# DCSource4V3.net
KiCad netlist of a schematic drawn in Altium Designer
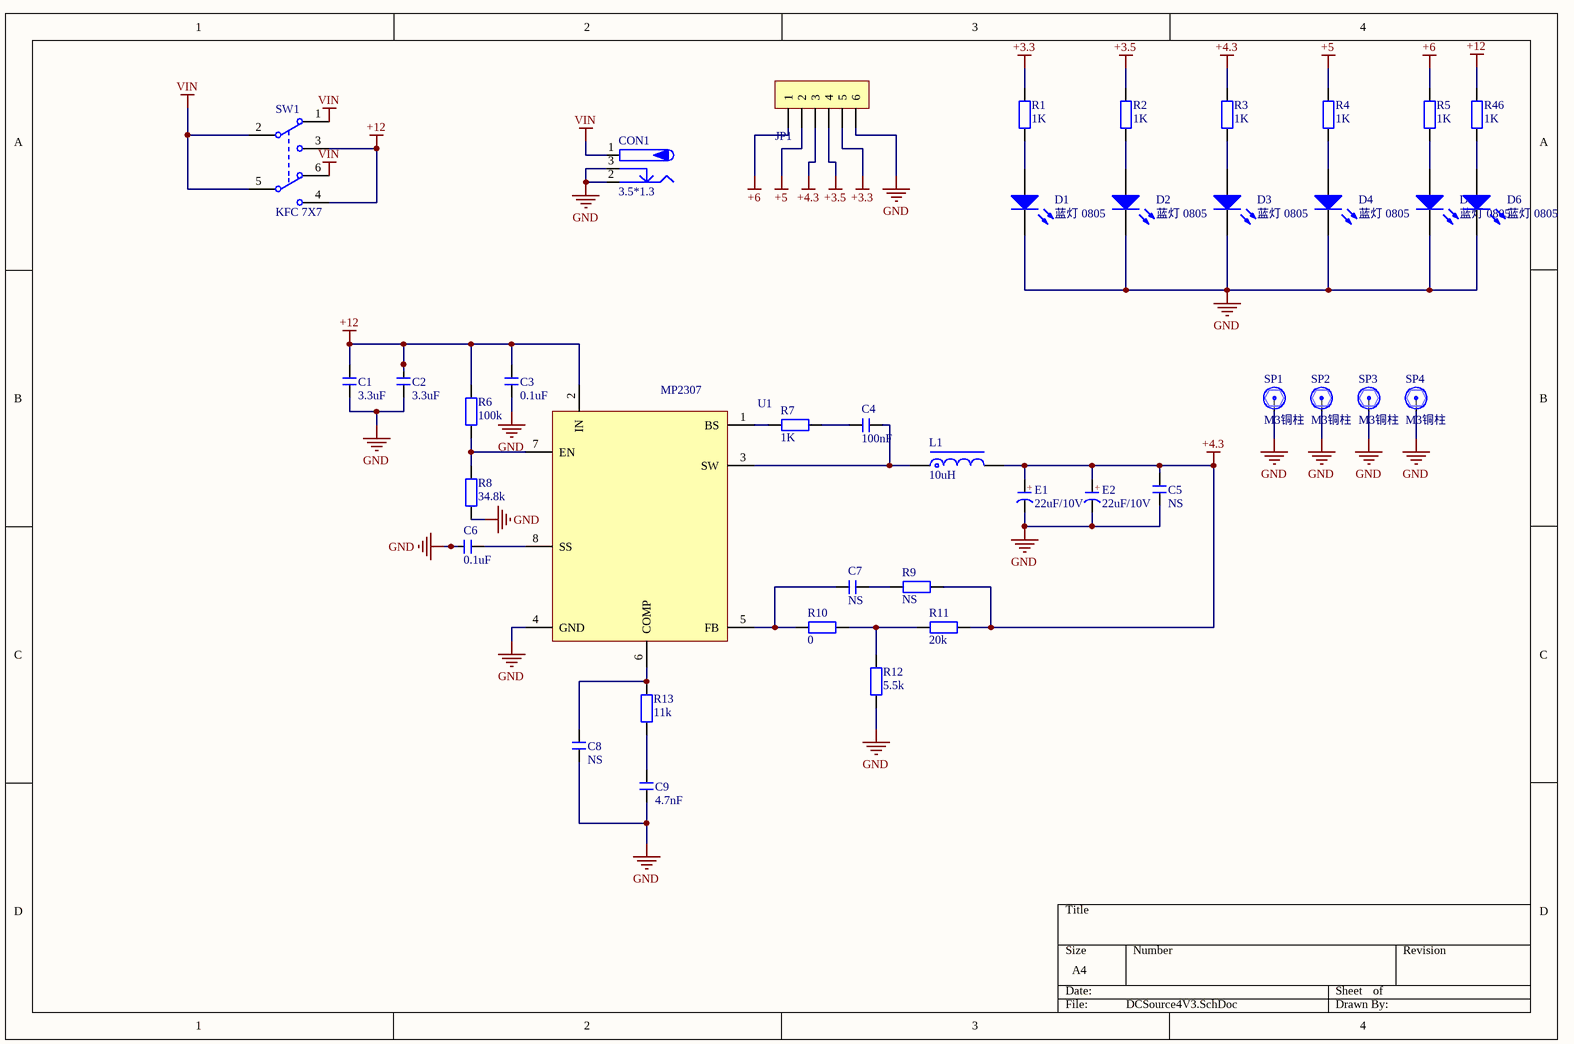
[diagram p0: DCSource4V3.SchDoc]

(export (version "E")
  (design (tool "Eeschema 10.0.6"))
  (components
    (comp (ref "C1")
      (value "3.3uF")
      (footprint "C 0805_L")
      (description "无极性贴片电容")
      (libsource (lib "电容-电阻-电感-电位器") (part "C"))
    )
    (comp (ref "C2")
      (value "3.3uF")
      (footprint "C 0805_L")
      (description "无极性贴片电容")
      (libsource (lib "电容-电阻-电感-电位器") (part "C"))
    )
    (comp (ref "C3")
      (value "0.1uF")
      (footprint "C 0805_L")
      (description "无极性贴片电容")
      (libsource (lib "电容-电阻-电感-电位器") (part "C"))
    )
    (comp (ref "C4")
      (value "100nF")
      (footprint "C 0805_L")
      (description "无极性贴片电容")
      (libsource (lib "电容-电阻-电感-电位器") (part "C"))
    )
    (comp (ref "C5")
      (value "NS")
      (footprint "C 0805_L")
      (description "无极性贴片电容")
      (libsource (lib "电容-电阻-电感-电位器") (part "C"))
    )
    (comp (ref "C6")
      (value "0.1uF")
      (footprint "C 0805_L")
      (description "无极性贴片电容")
      (libsource (lib "电容-电阻-电感-电位器") (part "C"))
    )
    (comp (ref "C7")
      (value "NS")
      (footprint "C 0805_L")
      (description "无极性贴片电容")
      (libsource (lib "电容-电阻-电感-电位器") (part "C"))
    )
    (comp (ref "C8")
      (value "NS")
      (footprint "C 0805_L")
      (description "无极性贴片电容")
      (libsource (lib "电容-电阻-电感-电位器") (part "C"))
    )
    (comp (ref "C9")
      (value "4.7nF")
      (footprint "C 0805_L")
      (description "无极性贴片电容")
      (libsource (lib "电容-电阻-电感-电位器") (part "C"))
    )
    (comp (ref "CON1")
      (value "3.5*1.3")
      (footprint "DC-005")
      (description "低压电源接口")
      (libsource (lib "接口") (part "P-DC"))
    )
    (comp (ref "D1")
      (value "蓝灯 0805")
      (footprint "0805_LED_S1")
      (description "发光二极管")
      (libsource (lib "JLC") (part "0805 蓝灯"))
    )
    (comp (ref "D2")
      (value "蓝灯 0805")
      (footprint "0805_LED_S1")
      (description "发光二极管")
      (libsource (lib "JLC") (part "0805 蓝灯"))
    )
    (comp (ref "D3")
      (value "蓝灯 0805")
      (footprint "0805_LED_S1")
      (description "发光二极管")
      (libsource (lib "JLC") (part "0805 蓝灯"))
    )
    (comp (ref "D4")
      (value "蓝灯 0805")
      (footprint "0805_LED_S1")
      (description "发光二极管")
      (libsource (lib "JLC") (part "0805 蓝灯"))
    )
    (comp (ref "D5")
      (value "蓝灯 0805")
      (footprint "0805_LED_S1")
      (description "发光二极管")
      (libsource (lib "JLC") (part "0805 蓝灯"))
    )
    (comp (ref "D6")
      (value "蓝灯 0805")
      (footprint "0805_LED_S1")
      (description "发光二极管")
      (libsource (lib "JLC") (part "0805 蓝灯"))
    )
    (comp (ref "E1")
      (value "22uF/10V")
      (footprint "CT 5*6 - C")
      (description "贴片固态电容")
      (libsource (lib "电容-电阻-电感-电位器") (part "C-CT"))
    )
    (comp (ref "E2")
      (value "22uF/10V")
      (footprint "CT 5*6 - C")
      (description "贴片固态电容")
      (libsource (lib "电容-电阻-电感-电位器") (part "C-CT"))
    )
    (comp (ref "JP1")
      (value "HDR-1X6")
      (footprint "XH2.54-WS-6P")
      (description "6P接插件")
      (libsource (lib "XH2.54") (part "Header 6"))
    )
    (comp (ref "L1")
      (value "10uH")
      (footprint "CD31")
      (description "贴片功率电感")
      (libsource (lib "电容-电阻-电感-电位器") (part "L-CD"))
    )
    (comp (ref "R1")
      (value "1K")
      (footprint "R 0805_L")
      (description "贴片电阻")
      (libsource (lib "电容-电阻-电感-电位器") (part "R"))
    )
    (comp (ref "R2")
      (value "1K")
      (footprint "R 0805_L")
      (description "贴片电阻")
      (libsource (lib "电容-电阻-电感-电位器") (part "R"))
    )
    (comp (ref "R3")
      (value "1K")
      (footprint "R 0805_L")
      (description "贴片电阻")
      (libsource (lib "电容-电阻-电感-电位器") (part "R"))
    )
    (comp (ref "R4")
      (value "1K")
      (footprint "R 0805_L")
      (description "贴片电阻")
      (libsource (lib "电容-电阻-电感-电位器") (part "R"))
    )
    (comp (ref "R5")
      (value "1K")
      (footprint "R 0805_L")
      (description "贴片电阻")
      (libsource (lib "电容-电阻-电感-电位器") (part "R"))
    )
    (comp (ref "R6")
      (value "100k")
      (footprint "R 0805_L")
      (description "贴片电阻")
      (libsource (lib "电容-电阻-电感-电位器") (part "R"))
    )
    (comp (ref "R7")
      (value "1K")
      (footprint "R 0805_L")
      (description "贴片电阻")
      (libsource (lib "电容-电阻-电感-电位器") (part "R"))
    )
    (comp (ref "R8")
      (value "34.8k")
      (footprint "R 0805_L")
      (description "贴片电阻")
      (libsource (lib "电容-电阻-电感-电位器") (part "R"))
    )
    (comp (ref "R9")
      (value "NS")
      (footprint "R 0805_L")
      (description "贴片电阻")
      (libsource (lib "电容-电阻-电感-电位器") (part "R"))
    )
    (comp (ref "R10")
      (value "0")
      (footprint "R 0805_L")
      (description "贴片电阻")
      (libsource (lib "电容-电阻-电感-电位器") (part "R"))
    )
    (comp (ref "R11")
      (value "20k")
      (footprint "R 0805_L")
      (description "贴片电阻")
      (libsource (lib "电容-电阻-电感-电位器") (part "R"))
    )
    (comp (ref "R12")
      (value "5.5k")
      (footprint "R 0805_L")
      (description "贴片电阻")
      (libsource (lib "电容-电阻-电感-电位器") (part "R"))
    )
    (comp (ref "R13")
      (value "11k")
      (footprint "R 0805_L")
      (description "贴片电阻")
      (libsource (lib "电容-电阻-电感-电位器") (part "R"))
    )
    (comp (ref "R46")
      (value "1K")
      (footprint "R 0805_L")
      (description "贴片电阻")
      (libsource (lib "电容-电阻-电感-电位器") (part "R"))
    )
    (comp (ref "SP1")
      (value "M3铜柱")
      (footprint "M3x4_L")
      (description "铜柱")
      (libsource (lib "铜柱-测试点-电池座-蜂鸣器") (part "铜柱小焊盘"))
    )
    (comp (ref "SP2")
      (value "M3铜柱")
      (footprint "M3x4_L")
      (description "铜柱")
      (libsource (lib "铜柱-测试点-电池座-蜂鸣器") (part "铜柱小焊盘"))
    )
    (comp (ref "SP3")
      (value "M3铜柱")
      (footprint "M3x4_L")
      (description "铜柱")
      (libsource (lib "铜柱-测试点-电池座-蜂鸣器") (part "铜柱小焊盘"))
    )
    (comp (ref "SP4")
      (value "M3铜柱")
      (footprint "M3x4_L")
      (description "铜柱")
      (libsource (lib "铜柱-测试点-电池座-蜂鸣器") (part "铜柱小焊盘"))
    )
    (comp (ref "SW1")
      (value "KFC 7X7")
      (footprint "KFC DIP-7X7")
      (description "7*7自锁开关")
      (libsource (lib "按键-开关") (part "KFC 7X7"))
    )
    (comp (ref "U1") (value "MP2307") (footprint "SOP8_M") (libsource (lib "Schlib1") (part "Component_1")))
  )
  (nets
    (net (code "1") (name "+3.3") (class "Default")
      (node (ref "JP1") (pin "5") (pinfunction "5_5") (pintype "passive"))
      (node (ref "R1") (pin "2") (pinfunction "2_2") (pintype "passive"))
    )
    (net (code "2") (name "+3.5") (class "Default")
      (node (ref "JP1") (pin "4") (pinfunction "4_4") (pintype "passive"))
      (node (ref "R2") (pin "2") (pinfunction "2_2") (pintype "passive"))
    )
    (net (code "3") (name "+4.3") (class "Default")
      (node (ref "C5") (pin "2") (pinfunction "2_2") (pintype "passive"))
      (node (ref "E1") (pin "1") (pinfunction "A_1") (pintype "passive"))
      (node (ref "E2") (pin "1") (pinfunction "A_1") (pintype "passive"))
      (node (ref "JP1") (pin "3") (pinfunction "3_3") (pintype "passive"))
      (node (ref "L1") (pin "2") (pinfunction "2_2") (pintype "passive"))
      (node (ref "R11") (pin "2") (pinfunction "2_2") (pintype "passive"))
      (node (ref "R3") (pin "2") (pinfunction "2_2") (pintype "passive"))
      (node (ref "R9") (pin "1") (pinfunction "1_1") (pintype "passive"))
    )
    (net (code "4") (name "+5") (class "Default")
      (node (ref "JP1") (pin "2") (pinfunction "2_2") (pintype "passive"))
      (node (ref "R4") (pin "2") (pinfunction "2_2") (pintype "passive"))
    )
    (net (code "5") (name "+6") (class "Default")
      (node (ref "JP1") (pin "1") (pinfunction "1_1") (pintype "passive"))
      (node (ref "R5") (pin "2") (pinfunction "2_2") (pintype "passive"))
    )
    (net (code "6") (name "+12") (class "Default")
      (node (ref "C1") (pin "2") (pinfunction "2_2") (pintype "passive"))
      (node (ref "C2") (pin "2") (pinfunction "2_2") (pintype "passive"))
      (node (ref "C3") (pin "2") (pinfunction "2_2") (pintype "passive"))
      (node (ref "R46") (pin "2") (pinfunction "2_2") (pintype "passive"))
      (node (ref "R6") (pin "2") (pinfunction "2_2") (pintype "passive"))
      (node (ref "SW1") (pin "3") (pinfunction "NO1_3") (pintype "passive"))
      (node (ref "SW1") (pin "4") (pinfunction "NO2_4") (pintype "passive"))
      (node (ref "U1") (pin "2") (pinfunction "IN_2") (pintype "passive"))
    )
    (net (code "7") (name "GND") (class "Default")
      (node (ref "C1") (pin "1") (pinfunction "1_1") (pintype "passive"))
      (node (ref "C2") (pin "1") (pinfunction "1_1") (pintype "passive"))
      (node (ref "C3") (pin "1") (pinfunction "1_1") (pintype "passive"))
      (node (ref "C5") (pin "1") (pinfunction "1_1") (pintype "passive"))
      (node (ref "C6") (pin "2") (pinfunction "2_2") (pintype "passive"))
      (node (ref "C8") (pin "1") (pinfunction "1_1") (pintype "passive"))
      (node (ref "C9") (pin "1") (pinfunction "1_1") (pintype "passive"))
      (node (ref "CON1") (pin "2") (pintype "power_in"))
      (node (ref "CON1") (pin "3") (pintype "power_in"))
      (node (ref "D1") (pin "K") (pinfunction "K_K") (pintype "passive"))
      (node (ref "D2") (pin "K") (pinfunction "K_K") (pintype "passive"))
      (node (ref "D3") (pin "K") (pinfunction "K_K") (pintype "passive"))
      (node (ref "D4") (pin "K") (pinfunction "K_K") (pintype "passive"))
      (node (ref "D5") (pin "K") (pinfunction "K_K") (pintype "passive"))
      (node (ref "D6") (pin "K") (pinfunction "K_K") (pintype "passive"))
      (node (ref "E1") (pin "2") (pinfunction "K_2") (pintype "passive"))
      (node (ref "E2") (pin "2") (pinfunction "K_2") (pintype "passive"))
      (node (ref "JP1") (pin "6") (pinfunction "6_6") (pintype "passive"))
      (node (ref "R12") (pin "1") (pinfunction "1_1") (pintype "passive"))
      (node (ref "R8") (pin "1") (pinfunction "1_1") (pintype "passive"))
      (node (ref "SP1") (pin "1") (pinfunction "1_1") (pintype "passive"))
      (node (ref "SP2") (pin "1") (pinfunction "1_1") (pintype "passive"))
      (node (ref "SP3") (pin "1") (pinfunction "1_1") (pintype "passive"))
      (node (ref "SP4") (pin "1") (pinfunction "1_1") (pintype "passive"))
      (node (ref "U1") (pin "4") (pinfunction "GND_4") (pintype "passive"))
    )
    (net (code "8") (name "Net-(C4-Pad1)") (class "Default")
      (node (ref "C4") (pin "1") (pinfunction "1_1") (pintype "passive"))
      (node (ref "R7") (pin "2") (pinfunction "2_2") (pintype "passive"))
    )
    (net (code "9") (name "Net-(C7-Pad2)") (class "Default")
      (node (ref "C7") (pin "2") (pinfunction "2_2") (pintype "passive"))
      (node (ref "R9") (pin "2") (pinfunction "2_2") (pintype "passive"))
    )
    (net (code "10") (name "Net-(C9-Pad2)") (class "Default")
      (node (ref "C9") (pin "2") (pinfunction "2_2") (pintype "passive"))
      (node (ref "R13") (pin "1") (pinfunction "1_1") (pintype "passive"))
    )
    (net (code "11") (name "Net-(D1-PadA)") (class "Default")
      (node (ref "D1") (pin "A") (pinfunction "A_A") (pintype "passive"))
      (node (ref "R1") (pin "1") (pinfunction "1_1") (pintype "passive"))
    )
    (net (code "12") (name "Net-(D2-PadA)") (class "Default")
      (node (ref "D2") (pin "A") (pinfunction "A_A") (pintype "passive"))
      (node (ref "R2") (pin "1") (pinfunction "1_1") (pintype "passive"))
    )
    (net (code "13") (name "Net-(D3-PadA)") (class "Default")
      (node (ref "D3") (pin "A") (pinfunction "A_A") (pintype "passive"))
      (node (ref "R3") (pin "1") (pinfunction "1_1") (pintype "passive"))
    )
    (net (code "14") (name "Net-(D4-PadA)") (class "Default")
      (node (ref "D4") (pin "A") (pinfunction "A_A") (pintype "passive"))
      (node (ref "R4") (pin "1") (pinfunction "1_1") (pintype "passive"))
    )
    (net (code "15") (name "Net-(D5-PadA)") (class "Default")
      (node (ref "D5") (pin "A") (pinfunction "A_A") (pintype "passive"))
      (node (ref "R5") (pin "1") (pinfunction "1_1") (pintype "passive"))
    )
    (net (code "16") (name "Net-(D6-PadA)") (class "Default")
      (node (ref "D6") (pin "A") (pinfunction "A_A") (pintype "passive"))
      (node (ref "R46") (pin "1") (pinfunction "1_1") (pintype "passive"))
    )
    (net (code "17") (name "Net-(R10-Pad2)") (class "Default")
      (node (ref "R10") (pin "2") (pinfunction "2_2") (pintype "passive"))
      (node (ref "R11") (pin "1") (pinfunction "1_1") (pintype "passive"))
      (node (ref "R12") (pin "2") (pinfunction "2_2") (pintype "passive"))
    )
    (net (code "18") (name "Net-(U1-BS)") (class "Default")
      (node (ref "R7") (pin "1") (pinfunction "1_1") (pintype "passive"))
      (node (ref "U1") (pin "1") (pinfunction "BS_1") (pintype "passive"))
    )
    (net (code "19") (name "Net-(U1-COMP)") (class "Default")
      (node (ref "C8") (pin "2") (pinfunction "2_2") (pintype "passive"))
      (node (ref "R13") (pin "2") (pinfunction "2_2") (pintype "passive"))
      (node (ref "U1") (pin "6") (pinfunction "COMP_6") (pintype "passive"))
    )
    (net (code "20") (name "Net-(U1-EN)") (class "Default")
      (node (ref "R6") (pin "1") (pinfunction "1_1") (pintype "passive"))
      (node (ref "R8") (pin "2") (pinfunction "2_2") (pintype "passive"))
      (node (ref "U1") (pin "7") (pinfunction "EN_7") (pintype "passive"))
    )
    (net (code "21") (name "Net-(U1-FB)") (class "Default")
      (node (ref "C7") (pin "1") (pinfunction "1_1") (pintype "passive"))
      (node (ref "R10") (pin "1") (pinfunction "1_1") (pintype "passive"))
      (node (ref "U1") (pin "5") (pinfunction "FB_5") (pintype "passive"))
    )
    (net (code "22") (name "Net-(U1-SS)") (class "Default")
      (node (ref "C6") (pin "1") (pinfunction "1_1") (pintype "passive"))
      (node (ref "U1") (pin "8") (pinfunction "SS_8") (pintype "passive"))
    )
    (net (code "23") (name "Net-(U1-SW)") (class "Default")
      (node (ref "C4") (pin "2") (pinfunction "2_2") (pintype "passive"))
      (node (ref "L1") (pin "1") (pinfunction "1_1") (pintype "passive"))
      (node (ref "U1") (pin "3") (pinfunction "SW_3") (pintype "passive"))
    )
    (net (code "24") (name "VIN") (class "Default")
      (node (ref "CON1") (pin "1") (pintype "power_in"))
      (node (ref "SW1") (pin "1") (pinfunction "NC1_1") (pintype "passive"))
      (node (ref "SW1") (pin "2") (pinfunction "COM2_2") (pintype "passive"))
      (node (ref "SW1") (pin "5") (pinfunction "COM2_5") (pintype "passive"))
      (node (ref "SW1") (pin "6") (pinfunction "NC2_6") (pintype "passive"))
    )
  )
)
